# design.net
KiCad netlist of a schematic drawn in Altium Designer
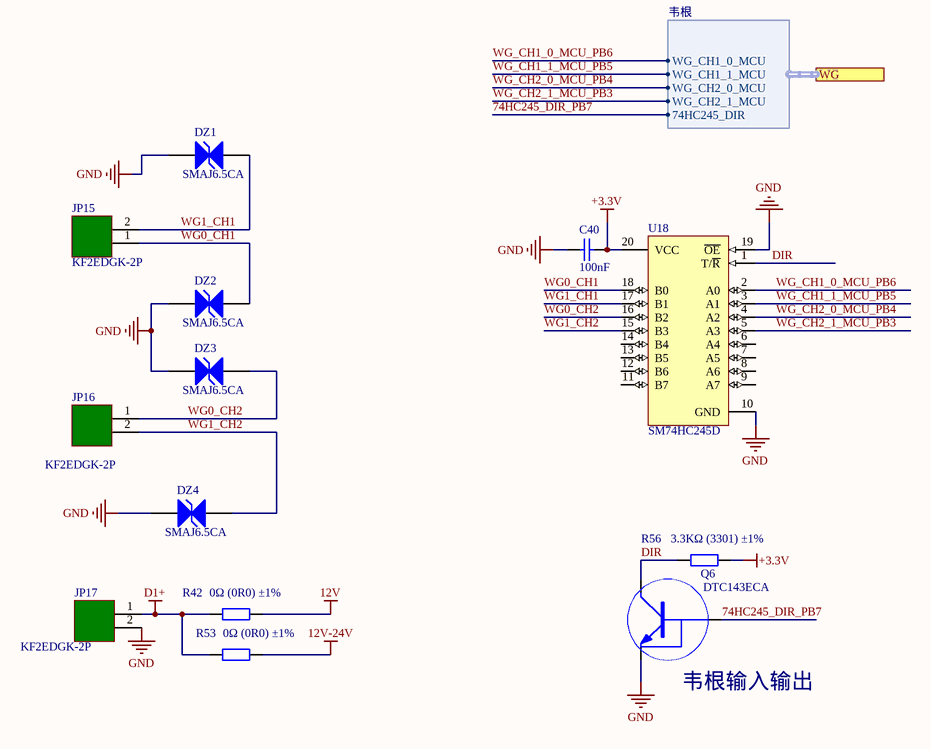
[diagram p0: 韦根输入输出.SchDoc]

(export (version "E")
  (design (tool "Eeschema 10.0.6"))
  (components
    (comp (ref "C40")
      (value "100nF")
      (footprint "0603_C")
      (description "贴片电容")
      (libsource (lib "Miscellaneous Devices LC") (part "0603 100nF (104) 10% 50V"))
    )
    (comp (ref "DZ1")
      (value "SMAJ6.5CA")
      (footprint "LC-SMA(DO-214AC)_S1")
      (description "TVS")
      (libsource (lib "Miscellaneous Devices LC") (part "SMB/DO-214AA P6SMB6.8CA"))
    )
    (comp (ref "DZ2")
      (value "SMAJ6.5CA")
      (footprint "LC-SMA(DO-214AC)_S1")
      (description "TVS")
      (libsource (lib "Miscellaneous Devices LC") (part "SMB/DO-214AA P6SMB6.8CA"))
    )
    (comp (ref "DZ3")
      (value "SMAJ6.5CA")
      (footprint "LC-SMA(DO-214AC)_S1")
      (description "TVS")
      (libsource (lib "Miscellaneous Devices LC") (part "SMB/DO-214AA P6SMB6.8CA"))
    )
    (comp (ref "DZ4")
      (value "SMAJ6.5CA")
      (footprint "LC-SMA(DO-214AC)_S1")
      (description "TVS")
      (libsource (lib "Miscellaneous Devices LC") (part "SMB/DO-214AA P6SMB6.8CA"))
    )
    (comp (ref "JP15")
      (value "KF2EDGK-2P")
      (footprint "KF2EDGK5.08W-2P")
      (libsource (lib "") (part "KF2EDGK-2P_1"))
    )
    (comp (ref "JP16")
      (value "KF2EDGK-2P")
      (footprint "KF2EDGK5.08W-2P")
      (libsource (lib "KF2EDGK") (part "KF2EDGK-2P"))
    )
    (comp (ref "JP17")
      (value "KF2EDGK-2P")
      (footprint "KF2EDGK5.08W-2P")
      (libsource (lib "KF2EDGK") (part "KF2EDGK-2P"))
    )
    (comp (ref "Q6") (value "DTC143ECA") (description "NPN集成三极管") (libsource (lib "this") (part "DTC143ECA")))
    (comp (ref "R42")
      (value "0Ω (0R0) ±1%")
      (footprint "1206_R")
      (description "贴片电阻")
      (libsource (lib "Miscellaneous Devices LC") (part "1206 0Ω (0R0) 1%"))
    )
    (comp (ref "R53")
      (value "0Ω (0R0) ±1%")
      (footprint "1206_R")
      (description "贴片电阻")
      (libsource (lib "Miscellaneous Devices LC") (part "1206 0Ω (0R0) 1%"))
    )
    (comp (ref "R56")
      (value "3.3KΩ (3301) ±1%")
      (footprint "0603_R")
      (description "贴片电阻")
      (libsource (lib "Miscellaneous Devices LC") (part "0603 3.3KΩ (3301) 1%"))
    )
    (comp (ref "U18")
      (value "SM74HC245D")
      (footprint "SOIC-20_300mil")
      (description "74系列逻辑芯片")
      (libsource (lib "Miscellaneous Devices LC") (part "74HC245D"))
    )
  )
  (nets
    (net (code "2") (name "+3.3V") (class "Default")
      (node (ref "C40") (pin "1") (pinfunction "1_1") (pintype "passive"))
      (node (ref "R56") (pin "2") (pinfunction "2_2") (pintype "passive"))
      (node (ref "U18") (pin "20") (pinfunction "VCC_20") (pintype "power_in"))
    )
    (net (code "3") (name "/74HC245_DIR_PB7") (class "Default")
      (node (ref "Q6") (pin "1") (pinfunction "IN_1") (pintype "passive"))
    )
    (net (code "4") (name "/DIR") (class "Default")
      (node (ref "Q6") (pin "3") (pinfunction "OUT_3") (pintype "passive"))
      (node (ref "R56") (pin "1") (pinfunction "1_1") (pintype "passive"))
      (node (ref "U18") (pin "1") (pinfunction "T/~{R}_1") (pintype "input"))
    )
    (net (code "5") (name "/WG0_CH1") (class "Default")
      (node (ref "DZ2") (pin "2") (pinfunction "K_2") (pintype "passive"))
      (node (ref "JP15") (pin "1") (pinfunction "1_1") (pintype "passive"))
      (node (ref "U18") (pin "18") (pinfunction "B0_18") (pintype "bidirectional"))
    )
    (net (code "6") (name "/WG0_CH2") (class "Default")
      (node (ref "DZ3") (pin "2") (pinfunction "K_2") (pintype "passive"))
      (node (ref "JP16") (pin "1") (pinfunction "1_1") (pintype "passive"))
      (node (ref "U18") (pin "16") (pinfunction "B2_16") (pintype "bidirectional"))
    )
    (net (code "7") (name "/WG1_CH1") (class "Default")
      (node (ref "DZ1") (pin "2") (pinfunction "K_2") (pintype "passive"))
      (node (ref "JP15") (pin "2") (pinfunction "2_2") (pintype "passive"))
      (node (ref "U18") (pin "17") (pinfunction "B1_17") (pintype "bidirectional"))
    )
    (net (code "8") (name "/WG1_CH2") (class "Default")
      (node (ref "DZ4") (pin "2") (pinfunction "K_2") (pintype "passive"))
      (node (ref "JP16") (pin "2") (pinfunction "2_2") (pintype "passive"))
      (node (ref "U18") (pin "15") (pinfunction "B3_15") (pintype "bidirectional"))
    )
    (net (code "9") (name "/WG_CH1_0_MCU_PB6") (class "Default")
      (node (ref "U18") (pin "2") (pinfunction "A0_2") (pintype "bidirectional"))
    )
    (net (code "10") (name "/WG_CH1_1_MCU_PB5") (class "Default")
      (node (ref "U18") (pin "3") (pinfunction "A1_3") (pintype "bidirectional"))
    )
    (net (code "11") (name "/WG_CH2_0_MCU_PB4") (class "Default")
      (node (ref "U18") (pin "4") (pinfunction "A2_4") (pintype "bidirectional"))
    )
    (net (code "12") (name "/WG_CH2_1_MCU_PB3") (class "Default")
      (node (ref "U18") (pin "5") (pinfunction "A3_5") (pintype "bidirectional"))
    )
    (net (code "14") (name "12V") (class "Default")
      (node (ref "R42") (pin "2") (pinfunction "2_2") (pintype "passive"))
    )
    (net (code "15") (name "12V-24V") (class "Default")
      (node (ref "R53") (pin "2") (pinfunction "2_2") (pintype "passive"))
    )
    (net (code "16") (name "D1+") (class "Default")
      (node (ref "JP17") (pin "1") (pinfunction "1_1") (pintype "passive"))
      (node (ref "R42") (pin "1") (pinfunction "1_1") (pintype "passive"))
      (node (ref "R53") (pin "1") (pinfunction "1_1") (pintype "passive"))
    )
    (net (code "17") (name "GND") (class "Default")
      (node (ref "C40") (pin "2") (pinfunction "2_2") (pintype "passive"))
      (node (ref "DZ1") (pin "1") (pinfunction "A_1") (pintype "passive"))
      (node (ref "DZ2") (pin "1") (pinfunction "A_1") (pintype "passive"))
      (node (ref "DZ3") (pin "1") (pinfunction "A_1") (pintype "passive"))
      (node (ref "DZ4") (pin "1") (pinfunction "A_1") (pintype "passive"))
      (node (ref "JP17") (pin "2") (pinfunction "2_2") (pintype "passive"))
      (node (ref "Q6") (pin "2") (pinfunction "GND_2") (pintype "passive"))
      (node (ref "U18") (pin "10") (pinfunction "GND_10") (pintype "power_in"))
      (node (ref "U18") (pin "19") (pinfunction "~{OE}_19") (pintype "input"))
    )
    (net (code "18") (name "unconnected-(U18-A4-Pad6)") (class "Default")
      (node (ref "U18") (pin "6") (pinfunction "A4_6") (pintype "bidirectional"))
    )
    (net (code "19") (name "unconnected-(U18-A5-Pad7)") (class "Default")
      (node (ref "U18") (pin "7") (pinfunction "A5_7") (pintype "bidirectional"))
    )
    (net (code "20") (name "unconnected-(U18-A6-Pad8)") (class "Default")
      (node (ref "U18") (pin "8") (pinfunction "A6_8") (pintype "bidirectional"))
    )
    (net (code "21") (name "unconnected-(U18-A7-Pad9)") (class "Default")
      (node (ref "U18") (pin "9") (pinfunction "A7_9") (pintype "bidirectional"))
    )
    (net (code "22") (name "unconnected-(U18-B4-Pad14)") (class "Default")
      (node (ref "U18") (pin "14") (pinfunction "B4_14") (pintype "bidirectional"))
    )
    (net (code "23") (name "unconnected-(U18-B5-Pad13)") (class "Default")
      (node (ref "U18") (pin "13") (pinfunction "B5_13") (pintype "bidirectional"))
    )
    (net (code "24") (name "unconnected-(U18-B6-Pad12)") (class "Default")
      (node (ref "U18") (pin "12") (pinfunction "B6_12") (pintype "bidirectional"))
    )
    (net (code "25") (name "unconnected-(U18-B7-Pad11)") (class "Default")
      (node (ref "U18") (pin "11") (pinfunction "B7_11") (pintype "bidirectional"))
    )
  )
)
